# CR99003.net
KiCad netlist of a schematic drawn in Altium Designer
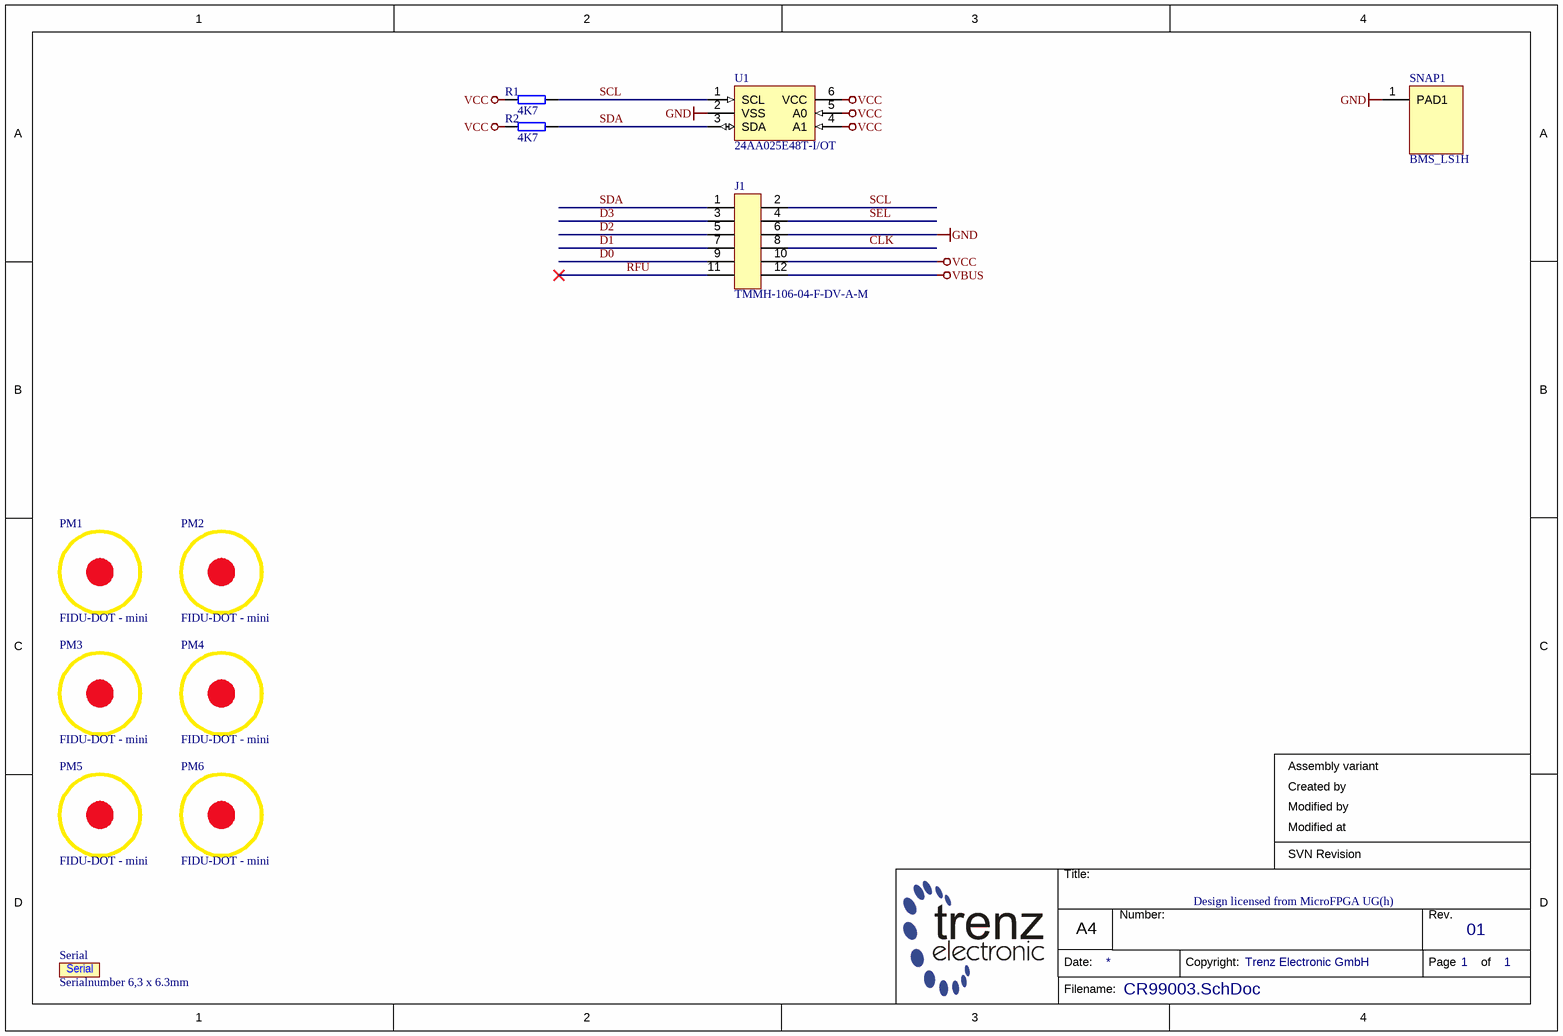
[diagram p0: CR99003.SchDoc]

(export (version "E")
  (design (tool "Eeschema 10.0.6"))
  (components
    (comp (ref "J1")
      (value "TMMH-106-04-F-DV-A-M")
      (footprint "TMMH-106-04-T-DV-A")
      (libsource (lib "TE") (part "CON-12"))
    )
    (comp (ref "PM1")
      (value "FIDU-DOT - mini")
      (footprint "FIDU-DOT - mini")
      (description "FIDU-DOT - MINI 0.5mm")
      (libsource (lib "TE") (part "FIDU-DOT - small"))
    )
    (comp (ref "PM2")
      (value "FIDU-DOT - mini")
      (footprint "FIDU-DOT - mini")
      (description "FIDU-DOT - MINI 0.5mm")
      (libsource (lib "TE") (part "FIDU-DOT - small"))
    )
    (comp (ref "PM3")
      (value "FIDU-DOT - mini")
      (footprint "FIDU-DOT - mini")
      (description "FIDU-DOT - MINI 0.5mm")
      (libsource (lib "TE") (part "FIDU-DOT - small"))
    )
    (comp (ref "PM4")
      (value "FIDU-DOT - mini")
      (footprint "FIDU-DOT - mini")
      (description "FIDU-DOT - MINI 0.5mm")
      (libsource (lib "TE") (part "FIDU-DOT - small"))
    )
    (comp (ref "PM5")
      (value "FIDU-DOT - mini")
      (footprint "FIDU-DOT - mini")
      (description "FIDU-DOT - MINI 0.5mm")
      (libsource (lib "TE") (part "FIDU-DOT - small"))
    )
    (comp (ref "PM6")
      (value "FIDU-DOT - mini")
      (footprint "FIDU-DOT - mini")
      (description "FIDU-DOT - MINI 0.5mm")
      (libsource (lib "TE") (part "FIDU-DOT - small"))
    )
    (comp (ref "R1")
      (value "4K7")
      (footprint "RESC1005X40N_V")
      (description "WID SMD 4K7 1% 0,063W BF 1005 (0402)")
      (fields (field (name "TOLERANCE") "1%"))
      (libsource (lib "TE") (part "RES"))
    )
    (comp (ref "R2")
      (value "4K7")
      (footprint "RESC1005X40N_V")
      (description "WID SMD 4K7 1% 0,063W BF 1005 (0402)")
      (fields (field (name "TOLERANCE") "1%"))
      (libsource (lib "TE") (part "RES"))
    )
    (comp (ref "Serial")
      (value "Serialnumber 6,3 x 6.3mm")
      (footprint "Serial_6.3x6.3mm")
      (libsource (lib "TE") (part "Serial"))
    )
    (comp (ref "SNAP1") (value "BMS_LS1H") (footprint "BMS_LS1H") (libsource (lib "BMOD") (part "BMS_LS1H")))
    (comp (ref "U1")
      (value "24AA025E48T-I/OT")
      (footprint "SOT95P280X145-6N")
      (libsource (lib "TE") (part "24AA025E48"))
    )
  )
  (nets
    (net (code "1") (name "/CLK") (class "Default")
      (node (ref "J1") (pin "8") (pinfunction "8_8") (pintype "passive"))
    )
    (net (code "2") (name "/D0") (class "Default")
      (node (ref "J1") (pin "9") (pinfunction "9_9") (pintype "passive"))
    )
    (net (code "3") (name "/D1") (class "Default")
      (node (ref "J1") (pin "7") (pinfunction "7_7") (pintype "passive"))
    )
    (net (code "4") (name "/D2") (class "Default")
      (node (ref "J1") (pin "5") (pinfunction "5_5") (pintype "passive"))
    )
    (net (code "5") (name "/D3") (class "Default")
      (node (ref "J1") (pin "3") (pinfunction "3_3") (pintype "passive"))
    )
    (net (code "6") (name "/RFU") (class "Default")
      (node (ref "J1") (pin "11") (pinfunction "11_11") (pintype "passive+no_connect"))
    )
    (net (code "7") (name "/SCL") (class "Default")
      (node (ref "J1") (pin "2") (pinfunction "2_2") (pintype "passive"))
      (node (ref "R1") (pin "2") (pinfunction "2_2") (pintype "passive"))
      (node (ref "U1") (pin "1") (pinfunction "SCL_1") (pintype "input"))
    )
    (net (code "8") (name "/SDA") (class "Default")
      (node (ref "J1") (pin "1") (pinfunction "1_1") (pintype "passive"))
      (node (ref "R2") (pin "2") (pinfunction "2_2") (pintype "passive"))
      (node (ref "U1") (pin "3") (pinfunction "SDA_3") (pintype "bidirectional"))
    )
    (net (code "9") (name "/SEL") (class "Default")
      (node (ref "J1") (pin "4") (pinfunction "4_4") (pintype "passive"))
    )
    (net (code "10") (name "GND") (class "Default")
      (node (ref "J1") (pin "6") (pinfunction "6_6") (pintype "passive"))
      (node (ref "SNAP1") (pin "1") (pinfunction "PAD1_1") (pintype "power_in"))
      (node (ref "U1") (pin "2") (pinfunction "VSS_2") (pintype "power_in"))
    )
    (net (code "11") (name "VBUS") (class "Default")
      (node (ref "J1") (pin "12") (pinfunction "12_12") (pintype "passive"))
    )
    (net (code "12") (name "VCC") (class "Default")
      (node (ref "J1") (pin "10") (pinfunction "10_10") (pintype "passive"))
      (node (ref "R1") (pin "1") (pinfunction "1_1") (pintype "passive"))
      (node (ref "R2") (pin "1") (pinfunction "1_1") (pintype "passive"))
      (node (ref "U1") (pin "4") (pinfunction "A1_4") (pintype "input"))
      (node (ref "U1") (pin "5") (pinfunction "A0_5") (pintype "input"))
      (node (ref "U1") (pin "6") (pinfunction "VCC_6") (pintype "power_in"))
    )
  )
)
